# light_module_v1.net
KiCad netlist of a schematic drawn in EAGLE
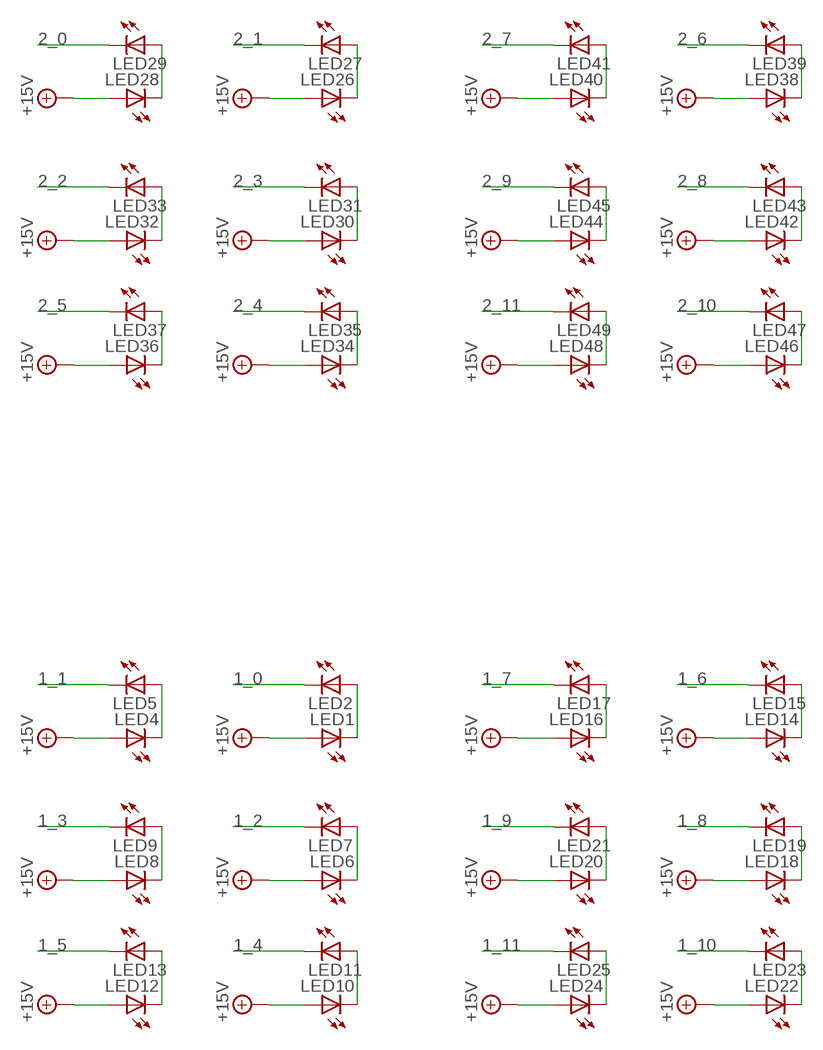
[diagram p0: schematic, sheet 1]
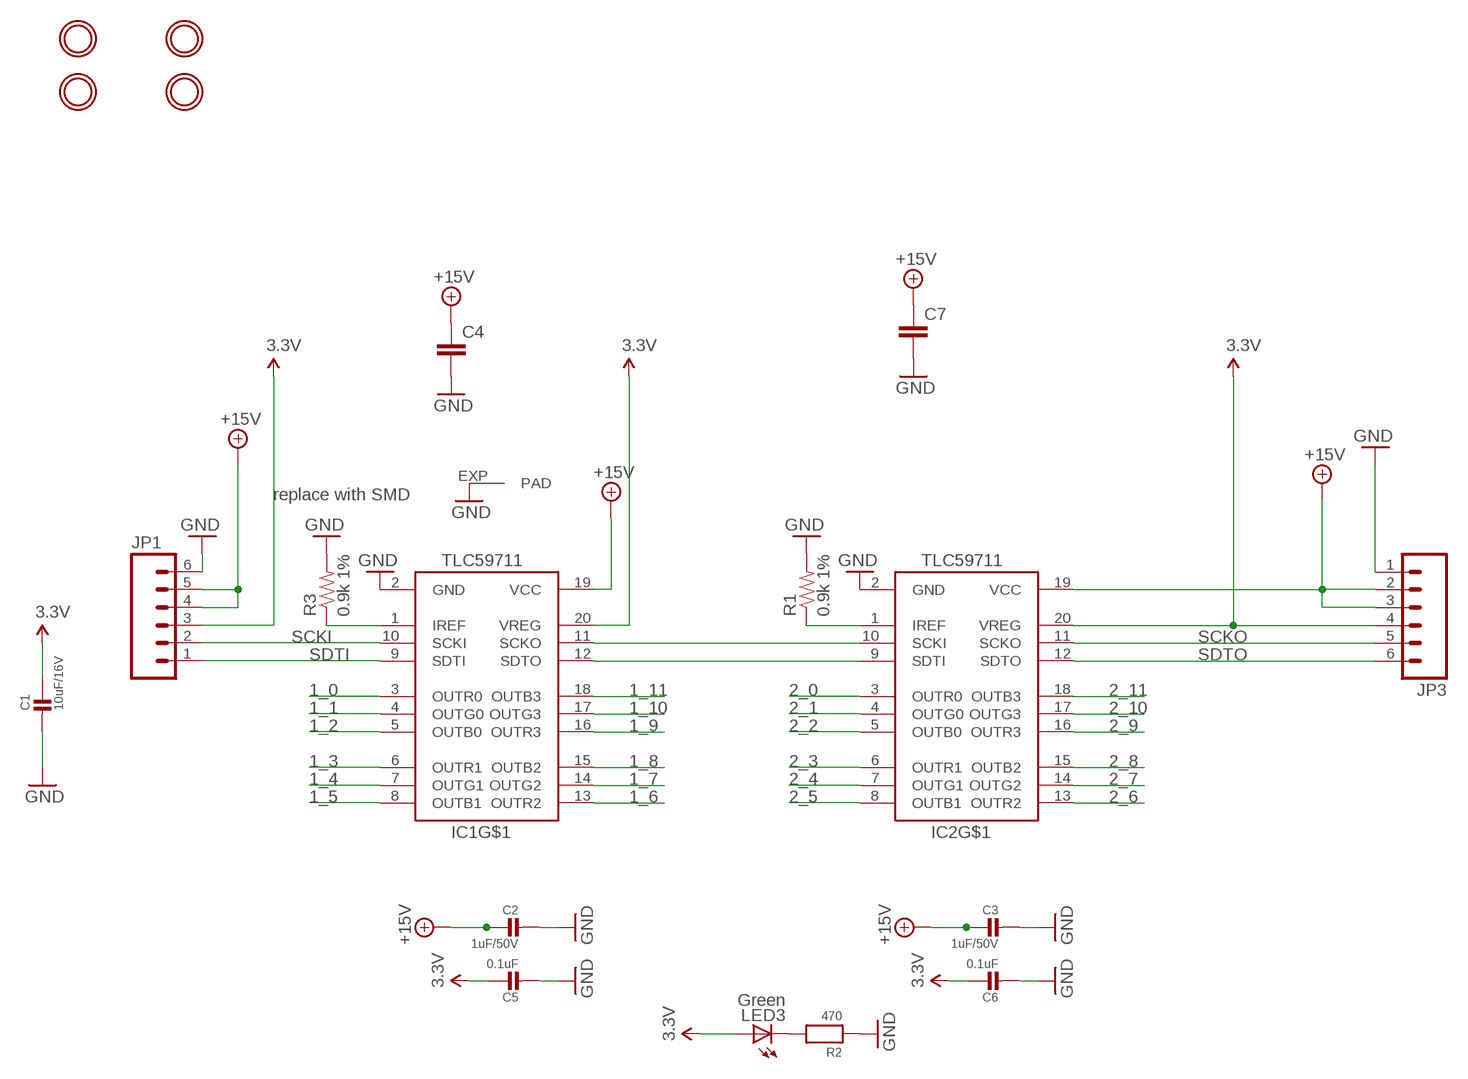
[diagram p1: schematic, sheet 2]

(export (version "E")
  (design (tool "Eeschema 10.0.6"))
  (components
    (comp (ref "C1")
      (value "10uF/16V")
      (footprint "eagle-import:0805")
      (libsource (lib "eagle-import") (part "CAP_CERAMIC0805"))
    )
    (comp (ref "C2")
      (value "1uF/50V")
      (footprint "eagle-import:0805")
      (libsource (lib "eagle-import") (part "CAP_CERAMIC0805"))
    )
    (comp (ref "C3")
      (value "1uF/50V")
      (footprint "eagle-import:0805")
      (libsource (lib "eagle-import") (part "CAP_CERAMIC0805"))
    )
    (comp (ref "C4")
      (value "CAP1206")
      (footprint "eagle-import:1206")
      (libsource (lib "eagle-import") (part "CAP1206"))
    )
    (comp (ref "C5")
      (value "0.1uF")
      (footprint "eagle-import:0805")
      (libsource (lib "eagle-import") (part "CAP_CERAMIC0805"))
    )
    (comp (ref "C6")
      (value "0.1uF")
      (footprint "eagle-import:0805")
      (libsource (lib "eagle-import") (part "CAP_CERAMIC0805"))
    )
    (comp (ref "C7")
      (value "CAP_")
      (footprint "eagle-import:AXIAL-5MM")
      (libsource (lib "eagle-import") (part "CAP_"))
    )
    (comp (ref "IC1")
      (value "TLC59711")
      (footprint "eagle-import:HTSSOP20DAP")
      (libsource (lib "eagle-import") (part "TLC59711"))
    )
    (comp (ref "IC2")
      (value "TLC59711")
      (footprint "eagle-import:HTSSOP20DAP")
      (libsource (lib "eagle-import") (part "TLC59711"))
    )
    (comp (ref "JP1")
      (value "M06SMD-STRAIGHT-COMBO-FEMALE")
      (footprint "eagle-import:1X06_SMD_STRAIGHT_COMBO")
      (libsource (lib "eagle-import") (part "M06SMD-STRAIGHT-COMBO-FEMALE"))
    )
    (comp (ref "JP3")
      (value "M06SMD-STRAIGHT-COMBO-FEMALE")
      (footprint "eagle-import:1X06_SMD_STRAIGHT_COMBO")
      (libsource (lib "eagle-import") (part "M06SMD-STRAIGHT-COMBO-FEMALE"))
    )
    (comp (ref "LED3")
      (value "Green")
      (footprint "eagle-import:CHIP-LED0805")
      (libsource (lib "eagle-import") (part "LEDCHIP-LED0805"))
    )
    (comp (ref "R1")
      (value "0.9k 1%")
      (footprint "eagle-import:1206")
      (libsource (lib "eagle-import") (part "RESISTOR1206"))
    )
    (comp (ref "R2")
      (value "470")
      (footprint "eagle-import:0805")
      (libsource (lib "eagle-import") (part "RESISTOR0805"))
    )
    (comp (ref "R3")
      (value "0.9k 1%")
      (footprint "eagle-import:1206")
      (libsource (lib "eagle-import") (part "RESISTOR1206"))
    )
    (comp (ref "U$1")
      (value "MOUNTINGHOLE2.5")
      (footprint "eagle-import:MOUNTINGHOLE_2.5_PLATED")
      (libsource (lib "eagle-import") (part "MOUNTINGHOLE2.5"))
    )
    (comp (ref "U$2")
      (value "MOUNTINGHOLE2.5")
      (footprint "eagle-import:MOUNTINGHOLE_2.5_PLATED")
      (libsource (lib "eagle-import") (part "MOUNTINGHOLE2.5"))
    )
    (comp (ref "U$3")
      (value "MOUNTINGHOLE2.5")
      (footprint "eagle-import:MOUNTINGHOLE_2.5_PLATED")
      (libsource (lib "eagle-import") (part "MOUNTINGHOLE2.5"))
    )
    (comp (ref "U$4")
      (value "MOUNTINGHOLE2.5")
      (footprint "eagle-import:MOUNTINGHOLE_2.5_PLATED")
      (libsource (lib "eagle-import") (part "MOUNTINGHOLE2.5"))
    )
    (comp (ref "LED1")
      (value "LED")
      (footprint "eagle-import:DS205")
      (libsource (lib "eagle-import") (part "digikey_LED"))
    )
    (comp (ref "LED2")
      (value "LED")
      (footprint "eagle-import:DS205")
      (libsource (lib "eagle-import") (part "digikey_LED"))
    )
    (comp (ref "LED4")
      (value "LED")
      (footprint "eagle-import:DS205")
      (libsource (lib "eagle-import") (part "digikey_LED"))
    )
    (comp (ref "LED5")
      (value "LED")
      (footprint "eagle-import:DS205")
      (libsource (lib "eagle-import") (part "digikey_LED"))
    )
    (comp (ref "LED6")
      (value "LED")
      (footprint "eagle-import:DS205")
      (libsource (lib "eagle-import") (part "digikey_LED"))
    )
    (comp (ref "LED7")
      (value "LED")
      (footprint "eagle-import:DS205")
      (libsource (lib "eagle-import") (part "digikey_LED"))
    )
    (comp (ref "LED8")
      (value "LED")
      (footprint "eagle-import:DS205")
      (libsource (lib "eagle-import") (part "digikey_LED"))
    )
    (comp (ref "LED9")
      (value "LED")
      (footprint "eagle-import:DS205")
      (libsource (lib "eagle-import") (part "digikey_LED"))
    )
    (comp (ref "LED10")
      (value "LED")
      (footprint "eagle-import:DS205")
      (libsource (lib "eagle-import") (part "digikey_LED"))
    )
    (comp (ref "LED11")
      (value "LED")
      (footprint "eagle-import:DS205")
      (libsource (lib "eagle-import") (part "digikey_LED"))
    )
    (comp (ref "LED12")
      (value "LED")
      (footprint "eagle-import:DS205")
      (libsource (lib "eagle-import") (part "digikey_LED"))
    )
    (comp (ref "LED13")
      (value "LED")
      (footprint "eagle-import:DS205")
      (libsource (lib "eagle-import") (part "digikey_LED"))
    )
    (comp (ref "LED14")
      (value "LED")
      (footprint "eagle-import:DS205")
      (libsource (lib "eagle-import") (part "digikey_LED"))
    )
    (comp (ref "LED15")
      (value "LED")
      (footprint "eagle-import:DS205")
      (libsource (lib "eagle-import") (part "digikey_LED"))
    )
    (comp (ref "LED16")
      (value "LED")
      (footprint "eagle-import:DS205")
      (libsource (lib "eagle-import") (part "digikey_LED"))
    )
    (comp (ref "LED17")
      (value "LED")
      (footprint "eagle-import:DS205")
      (libsource (lib "eagle-import") (part "digikey_LED"))
    )
    (comp (ref "LED18")
      (value "LED")
      (footprint "eagle-import:DS205")
      (libsource (lib "eagle-import") (part "digikey_LED"))
    )
    (comp (ref "LED19")
      (value "LED")
      (footprint "eagle-import:DS205")
      (libsource (lib "eagle-import") (part "digikey_LED"))
    )
    (comp (ref "LED20")
      (value "LED")
      (footprint "eagle-import:DS205")
      (libsource (lib "eagle-import") (part "digikey_LED"))
    )
    (comp (ref "LED21")
      (value "LED")
      (footprint "eagle-import:DS205")
      (libsource (lib "eagle-import") (part "digikey_LED"))
    )
    (comp (ref "LED22")
      (value "LED")
      (footprint "eagle-import:DS205")
      (libsource (lib "eagle-import") (part "digikey_LED"))
    )
    (comp (ref "LED23")
      (value "LED")
      (footprint "eagle-import:DS205")
      (libsource (lib "eagle-import") (part "digikey_LED"))
    )
    (comp (ref "LED24")
      (value "LED")
      (footprint "eagle-import:DS205")
      (libsource (lib "eagle-import") (part "digikey_LED"))
    )
    (comp (ref "LED25")
      (value "LED")
      (footprint "eagle-import:DS205")
      (libsource (lib "eagle-import") (part "digikey_LED"))
    )
    (comp (ref "LED26")
      (value "LED")
      (footprint "eagle-import:DS205")
      (libsource (lib "eagle-import") (part "digikey_LED"))
    )
    (comp (ref "LED27")
      (value "LED")
      (footprint "eagle-import:DS205")
      (libsource (lib "eagle-import") (part "digikey_LED"))
    )
    (comp (ref "LED28")
      (value "LED")
      (footprint "eagle-import:DS205")
      (libsource (lib "eagle-import") (part "digikey_LED"))
    )
    (comp (ref "LED29")
      (value "LED")
      (footprint "eagle-import:DS205")
      (libsource (lib "eagle-import") (part "digikey_LED"))
    )
    (comp (ref "LED30")
      (value "LED")
      (footprint "eagle-import:DS205")
      (libsource (lib "eagle-import") (part "digikey_LED"))
    )
    (comp (ref "LED31")
      (value "LED")
      (footprint "eagle-import:DS205")
      (libsource (lib "eagle-import") (part "digikey_LED"))
    )
    (comp (ref "LED32")
      (value "LED")
      (footprint "eagle-import:DS205")
      (libsource (lib "eagle-import") (part "digikey_LED"))
    )
    (comp (ref "LED33")
      (value "LED")
      (footprint "eagle-import:DS205")
      (libsource (lib "eagle-import") (part "digikey_LED"))
    )
    (comp (ref "LED34")
      (value "LED")
      (footprint "eagle-import:DS205")
      (libsource (lib "eagle-import") (part "digikey_LED"))
    )
    (comp (ref "LED35")
      (value "LED")
      (footprint "eagle-import:DS205")
      (libsource (lib "eagle-import") (part "digikey_LED"))
    )
    (comp (ref "LED36")
      (value "LED")
      (footprint "eagle-import:DS205")
      (libsource (lib "eagle-import") (part "digikey_LED"))
    )
    (comp (ref "LED37")
      (value "LED")
      (footprint "eagle-import:DS205")
      (libsource (lib "eagle-import") (part "digikey_LED"))
    )
    (comp (ref "LED38")
      (value "LED")
      (footprint "eagle-import:DS205")
      (libsource (lib "eagle-import") (part "digikey_LED"))
    )
    (comp (ref "LED39")
      (value "LED")
      (footprint "eagle-import:DS205")
      (libsource (lib "eagle-import") (part "digikey_LED"))
    )
    (comp (ref "LED40")
      (value "LED")
      (footprint "eagle-import:DS205")
      (libsource (lib "eagle-import") (part "digikey_LED"))
    )
    (comp (ref "LED41")
      (value "LED")
      (footprint "eagle-import:DS205")
      (libsource (lib "eagle-import") (part "digikey_LED"))
    )
    (comp (ref "LED42")
      (value "LED")
      (footprint "eagle-import:DS205")
      (libsource (lib "eagle-import") (part "digikey_LED"))
    )
    (comp (ref "LED43")
      (value "LED")
      (footprint "eagle-import:DS205")
      (libsource (lib "eagle-import") (part "digikey_LED"))
    )
    (comp (ref "LED44")
      (value "LED")
      (footprint "eagle-import:DS205")
      (libsource (lib "eagle-import") (part "digikey_LED"))
    )
    (comp (ref "LED45")
      (value "LED")
      (footprint "eagle-import:DS205")
      (libsource (lib "eagle-import") (part "digikey_LED"))
    )
    (comp (ref "LED46")
      (value "LED")
      (footprint "eagle-import:DS205")
      (libsource (lib "eagle-import") (part "digikey_LED"))
    )
    (comp (ref "LED47")
      (value "LED")
      (footprint "eagle-import:DS205")
      (libsource (lib "eagle-import") (part "digikey_LED"))
    )
    (comp (ref "LED48")
      (value "LED")
      (footprint "eagle-import:DS205")
      (libsource (lib "eagle-import") (part "digikey_LED"))
    )
    (comp (ref "LED49")
      (value "LED")
      (footprint "eagle-import:DS205")
      (libsource (lib "eagle-import") (part "digikey_LED"))
    )
  )
  (nets
    (net (code "1") (name "+15V") (class "Default")
      (node (ref "C2") (pin "1") (pinfunction "P$1_1") (pintype "passive"))
      (node (ref "C3") (pin "1") (pinfunction "P$1_1") (pintype "passive"))
      (node (ref "C4") (pin "1") (pinfunction "1_1") (pintype "passive"))
      (node (ref "C7") (pin "P$1") (pinfunction "1_P$1") (pintype "passive"))
      (node (ref "IC1") (pin "19") (pinfunction "VCC_19") (pintype "power_in"))
      (node (ref "IC2") (pin "19") (pinfunction "VCC_19") (pintype "power_in"))
      (node (ref "JP1") (pin "4") (pinfunction "4_4") (pintype "passive"))
      (node (ref "JP1") (pin "5") (pinfunction "5_5") (pintype "passive"))
      (node (ref "JP3") (pin "2") (pinfunction "2_2") (pintype "passive"))
      (node (ref "JP3") (pin "3") (pinfunction "3_3") (pintype "passive"))
      (node (ref "LED1") (pin "P$1") (pinfunction "A_P$1") (pintype "passive"))
      (node (ref "LED10") (pin "P$1") (pinfunction "A_P$1") (pintype "passive"))
      (node (ref "LED12") (pin "P$1") (pinfunction "A_P$1") (pintype "passive"))
      (node (ref "LED14") (pin "P$1") (pinfunction "A_P$1") (pintype "passive"))
      (node (ref "LED16") (pin "P$1") (pinfunction "A_P$1") (pintype "passive"))
      (node (ref "LED18") (pin "P$1") (pinfunction "A_P$1") (pintype "passive"))
      (node (ref "LED20") (pin "P$1") (pinfunction "A_P$1") (pintype "passive"))
      (node (ref "LED22") (pin "P$1") (pinfunction "A_P$1") (pintype "passive"))
      (node (ref "LED24") (pin "P$1") (pinfunction "A_P$1") (pintype "passive"))
      (node (ref "LED26") (pin "P$1") (pinfunction "A_P$1") (pintype "passive"))
      (node (ref "LED28") (pin "P$1") (pinfunction "A_P$1") (pintype "passive"))
      (node (ref "LED30") (pin "P$1") (pinfunction "A_P$1") (pintype "passive"))
      (node (ref "LED32") (pin "P$1") (pinfunction "A_P$1") (pintype "passive"))
      (node (ref "LED34") (pin "P$1") (pinfunction "A_P$1") (pintype "passive"))
      (node (ref "LED36") (pin "P$1") (pinfunction "A_P$1") (pintype "passive"))
      (node (ref "LED38") (pin "P$1") (pinfunction "A_P$1") (pintype "passive"))
      (node (ref "LED4") (pin "P$1") (pinfunction "A_P$1") (pintype "passive"))
      (node (ref "LED40") (pin "P$1") (pinfunction "A_P$1") (pintype "passive"))
      (node (ref "LED42") (pin "P$1") (pinfunction "A_P$1") (pintype "passive"))
      (node (ref "LED44") (pin "P$1") (pinfunction "A_P$1") (pintype "passive"))
      (node (ref "LED46") (pin "P$1") (pinfunction "A_P$1") (pintype "passive"))
      (node (ref "LED48") (pin "P$1") (pinfunction "A_P$1") (pintype "passive"))
      (node (ref "LED6") (pin "P$1") (pinfunction "A_P$1") (pintype "passive"))
      (node (ref "LED8") (pin "P$1") (pinfunction "A_P$1") (pintype "passive"))
    )
    (net (code "2") (name "1_0") (class "Default")
      (node (ref "IC1") (pin "3") (pinfunction "OUTR0_3") (pintype "open_collector"))
      (node (ref "LED2") (pin "P$2") (pinfunction "C_P$2") (pintype "passive"))
    )
    (net (code "3") (name "1_1") (class "Default")
      (node (ref "IC1") (pin "4") (pinfunction "OUTG0_4") (pintype "open_collector"))
      (node (ref "LED5") (pin "P$2") (pinfunction "C_P$2") (pintype "passive"))
    )
    (net (code "4") (name "1_2") (class "Default")
      (node (ref "IC1") (pin "5") (pinfunction "OUTB0_5") (pintype "open_collector"))
      (node (ref "LED7") (pin "P$2") (pinfunction "C_P$2") (pintype "passive"))
    )
    (net (code "5") (name "1_3") (class "Default")
      (node (ref "IC1") (pin "6") (pinfunction "OUTR1_6") (pintype "open_collector"))
      (node (ref "LED9") (pin "P$2") (pinfunction "C_P$2") (pintype "passive"))
    )
    (net (code "6") (name "1_4") (class "Default")
      (node (ref "IC1") (pin "7") (pinfunction "OUTG1_7") (pintype "open_collector"))
      (node (ref "LED11") (pin "P$2") (pinfunction "C_P$2") (pintype "passive"))
    )
    (net (code "7") (name "1_5") (class "Default")
      (node (ref "IC1") (pin "8") (pinfunction "OUTB1_8") (pintype "open_collector"))
      (node (ref "LED13") (pin "P$2") (pinfunction "C_P$2") (pintype "passive"))
    )
    (net (code "8") (name "1_6") (class "Default")
      (node (ref "IC1") (pin "13") (pinfunction "OUTR2_13") (pintype "open_collector"))
      (node (ref "LED15") (pin "P$2") (pinfunction "C_P$2") (pintype "passive"))
    )
    (net (code "9") (name "1_7") (class "Default")
      (node (ref "IC1") (pin "14") (pinfunction "OUTG2_14") (pintype "open_collector"))
      (node (ref "LED17") (pin "P$2") (pinfunction "C_P$2") (pintype "passive"))
    )
    (net (code "10") (name "1_8") (class "Default")
      (node (ref "IC1") (pin "15") (pinfunction "OUTB2_15") (pintype "open_collector"))
      (node (ref "LED19") (pin "P$2") (pinfunction "C_P$2") (pintype "passive"))
    )
    (net (code "11") (name "1_9") (class "Default")
      (node (ref "IC1") (pin "16") (pinfunction "OUTR3_16") (pintype "open_collector"))
      (node (ref "LED21") (pin "P$2") (pinfunction "C_P$2") (pintype "passive"))
    )
    (net (code "12") (name "1_10") (class "Default")
      (node (ref "IC1") (pin "17") (pinfunction "OUTG3_17") (pintype "open_collector"))
      (node (ref "LED23") (pin "P$2") (pinfunction "C_P$2") (pintype "passive"))
    )
    (net (code "13") (name "1_11") (class "Default")
      (node (ref "IC1") (pin "18") (pinfunction "OUTB3_18") (pintype "open_collector"))
      (node (ref "LED25") (pin "P$2") (pinfunction "C_P$2") (pintype "passive"))
    )
    (net (code "14") (name "2_0") (class "Default")
      (node (ref "IC2") (pin "3") (pinfunction "OUTR0_3") (pintype "open_collector"))
      (node (ref "LED29") (pin "P$2") (pinfunction "C_P$2") (pintype "passive"))
    )
    (net (code "15") (name "2_1") (class "Default")
      (node (ref "IC2") (pin "4") (pinfunction "OUTG0_4") (pintype "open_collector"))
      (node (ref "LED27") (pin "P$2") (pinfunction "C_P$2") (pintype "passive"))
    )
    (net (code "16") (name "2_2") (class "Default")
      (node (ref "IC2") (pin "5") (pinfunction "OUTB0_5") (pintype "open_collector"))
      (node (ref "LED33") (pin "P$2") (pinfunction "C_P$2") (pintype "passive"))
    )
    (net (code "17") (name "2_3") (class "Default")
      (node (ref "IC2") (pin "6") (pinfunction "OUTR1_6") (pintype "open_collector"))
      (node (ref "LED31") (pin "P$2") (pinfunction "C_P$2") (pintype "passive"))
    )
    (net (code "18") (name "2_4") (class "Default")
      (node (ref "IC2") (pin "7") (pinfunction "OUTG1_7") (pintype "open_collector"))
      (node (ref "LED35") (pin "P$2") (pinfunction "C_P$2") (pintype "passive"))
    )
    (net (code "19") (name "2_5") (class "Default")
      (node (ref "IC2") (pin "8") (pinfunction "OUTB1_8") (pintype "open_collector"))
      (node (ref "LED37") (pin "P$2") (pinfunction "C_P$2") (pintype "passive"))
    )
    (net (code "20") (name "2_6") (class "Default")
      (node (ref "IC2") (pin "13") (pinfunction "OUTR2_13") (pintype "open_collector"))
      (node (ref "LED39") (pin "P$2") (pinfunction "C_P$2") (pintype "passive"))
    )
    (net (code "21") (name "2_7") (class "Default")
      (node (ref "IC2") (pin "14") (pinfunction "OUTG2_14") (pintype "open_collector"))
      (node (ref "LED41") (pin "P$2") (pinfunction "C_P$2") (pintype "passive"))
    )
    (net (code "22") (name "2_8") (class "Default")
      (node (ref "IC2") (pin "15") (pinfunction "OUTB2_15") (pintype "open_collector"))
      (node (ref "LED43") (pin "P$2") (pinfunction "C_P$2") (pintype "passive"))
    )
    (net (code "23") (name "2_9") (class "Default")
      (node (ref "IC2") (pin "16") (pinfunction "OUTR3_16") (pintype "open_collector"))
      (node (ref "LED45") (pin "P$2") (pinfunction "C_P$2") (pintype "passive"))
    )
    (net (code "24") (name "2_10") (class "Default")
      (node (ref "IC2") (pin "17") (pinfunction "OUTG3_17") (pintype "open_collector"))
      (node (ref "LED47") (pin "P$2") (pinfunction "C_P$2") (pintype "passive"))
    )
    (net (code "25") (name "2_11") (class "Default")
      (node (ref "IC2") (pin "18") (pinfunction "OUTB3_18") (pintype "open_collector"))
      (node (ref "LED49") (pin "P$2") (pinfunction "C_P$2") (pintype "passive"))
    )
    (net (code "26") (name "3.3V") (class "Default")
      (node (ref "C1") (pin "1") (pinfunction "P$1_1") (pintype "passive"))
      (node (ref "C5") (pin "1") (pinfunction "P$1_1") (pintype "passive"))
      (node (ref "C6") (pin "1") (pinfunction "P$1_1") (pintype "passive"))
      (node (ref "IC1") (pin "20") (pinfunction "VREG_20") (pintype "bidirectional"))
      (node (ref "IC2") (pin "20") (pinfunction "VREG_20") (pintype "bidirectional"))
      (node (ref "JP1") (pin "3") (pinfunction "3_3") (pintype "passive"))
      (node (ref "JP3") (pin "4") (pinfunction "4_4") (pintype "passive"))
      (node (ref "LED3") (pin "A") (pinfunction "A_A") (pintype "passive"))
    )
    (net (code "27") (name "GND") (class "Default")
      (node (ref "C1") (pin "2") (pinfunction "P$2_2") (pintype "passive"))
      (node (ref "C2") (pin "2") (pinfunction "P$2_2") (pintype "passive"))
      (node (ref "C3") (pin "2") (pinfunction "P$2_2") (pintype "passive"))
      (node (ref "C4") (pin "2") (pinfunction "2_2") (pintype "passive"))
      (node (ref "C5") (pin "2") (pinfunction "P$2_2") (pintype "passive"))
      (node (ref "C6") (pin "2") (pinfunction "P$2_2") (pintype "passive"))
      (node (ref "C7") (pin "P$2") (pinfunction "2_P$2") (pintype "passive"))
      (node (ref "IC1") (pin "2") (pinfunction "GND_2") (pintype "power_in"))
      (node (ref "IC1") (pin "EXP") (pinfunction "PAD_EXP") (pintype "passive"))
      (node (ref "IC2") (pin "2") (pinfunction "GND_2") (pintype "power_in"))
      (node (ref "JP1") (pin "6") (pinfunction "6_6") (pintype "passive"))
      (node (ref "JP3") (pin "1") (pinfunction "1_1") (pintype "passive"))
      (node (ref "R1") (pin "2") (pinfunction "2_2") (pintype "passive"))
      (node (ref "R2") (pin "1") (pinfunction "1_1") (pintype "passive"))
      (node (ref "R3") (pin "2") (pinfunction "2_2") (pintype "passive"))
    )
    (net (code "28") (name "Net-(IC1A-IREF)") (class "Default")
      (node (ref "IC1") (pin "1") (pinfunction "IREF_1") (pintype "bidirectional"))
      (node (ref "R3") (pin "1") (pinfunction "1_1") (pintype "passive"))
    )
    (net (code "29") (name "Net-(IC1A-SCKO)") (class "Default")
      (node (ref "IC1") (pin "11") (pinfunction "SCKO_11") (pintype "output"))
      (node (ref "IC2") (pin "10") (pinfunction "SCKI_10") (pintype "input"))
    )
    (net (code "30") (name "Net-(IC1A-SDTO)") (class "Default")
      (node (ref "IC1") (pin "12") (pinfunction "SDTO_12") (pintype "output"))
      (node (ref "IC2") (pin "9") (pinfunction "SDTI_9") (pintype "input"))
    )
    (net (code "31") (name "Net-(IC2A-IREF)") (class "Default")
      (node (ref "IC2") (pin "1") (pinfunction "IREF_1") (pintype "bidirectional"))
      (node (ref "R1") (pin "1") (pinfunction "1_1") (pintype "passive"))
    )
    (net (code "32") (name "Net-(LED1-C)") (class "Default")
      (node (ref "LED1") (pin "P$2") (pinfunction "C_P$2") (pintype "passive"))
      (node (ref "LED2") (pin "P$1") (pinfunction "A_P$1") (pintype "passive"))
    )
    (net (code "33") (name "Net-(LED3-PadC)") (class "Default")
      (node (ref "LED3") (pin "C") (pinfunction "C_C") (pintype "passive"))
      (node (ref "R2") (pin "2") (pinfunction "2_2") (pintype "passive"))
    )
    (net (code "34") (name "Net-(LED4-C)") (class "Default")
      (node (ref "LED4") (pin "P$2") (pinfunction "C_P$2") (pintype "passive"))
      (node (ref "LED5") (pin "P$1") (pinfunction "A_P$1") (pintype "passive"))
    )
    (net (code "35") (name "Net-(LED6-C)") (class "Default")
      (node (ref "LED6") (pin "P$2") (pinfunction "C_P$2") (pintype "passive"))
      (node (ref "LED7") (pin "P$1") (pinfunction "A_P$1") (pintype "passive"))
    )
    (net (code "36") (name "Net-(LED8-C)") (class "Default")
      (node (ref "LED8") (pin "P$2") (pinfunction "C_P$2") (pintype "passive"))
      (node (ref "LED9") (pin "P$1") (pinfunction "A_P$1") (pintype "passive"))
    )
    (net (code "37") (name "Net-(LED10-C)") (class "Default")
      (node (ref "LED10") (pin "P$2") (pinfunction "C_P$2") (pintype "passive"))
      (node (ref "LED11") (pin "P$1") (pinfunction "A_P$1") (pintype "passive"))
    )
    (net (code "38") (name "Net-(LED12-C)") (class "Default")
      (node (ref "LED12") (pin "P$2") (pinfunction "C_P$2") (pintype "passive"))
      (node (ref "LED13") (pin "P$1") (pinfunction "A_P$1") (pintype "passive"))
    )
    (net (code "39") (name "Net-(LED14-C)") (class "Default")
      (node (ref "LED14") (pin "P$2") (pinfunction "C_P$2") (pintype "passive"))
      (node (ref "LED15") (pin "P$1") (pinfunction "A_P$1") (pintype "passive"))
    )
    (net (code "40") (name "Net-(LED16-C)") (class "Default")
      (node (ref "LED16") (pin "P$2") (pinfunction "C_P$2") (pintype "passive"))
      (node (ref "LED17") (pin "P$1") (pinfunction "A_P$1") (pintype "passive"))
    )
    (net (code "41") (name "Net-(LED18-C)") (class "Default")
      (node (ref "LED18") (pin "P$2") (pinfunction "C_P$2") (pintype "passive"))
      (node (ref "LED19") (pin "P$1") (pinfunction "A_P$1") (pintype "passive"))
    )
    (net (code "42") (name "Net-(LED20-C)") (class "Default")
      (node (ref "LED20") (pin "P$2") (pinfunction "C_P$2") (pintype "passive"))
      (node (ref "LED21") (pin "P$1") (pinfunction "A_P$1") (pintype "passive"))
    )
    (net (code "43") (name "Net-(LED22-C)") (class "Default")
      (node (ref "LED22") (pin "P$2") (pinfunction "C_P$2") (pintype "passive"))
      (node (ref "LED23") (pin "P$1") (pinfunction "A_P$1") (pintype "passive"))
    )
    (net (code "44") (name "Net-(LED24-C)") (class "Default")
      (node (ref "LED24") (pin "P$2") (pinfunction "C_P$2") (pintype "passive"))
      (node (ref "LED25") (pin "P$1") (pinfunction "A_P$1") (pintype "passive"))
    )
    (net (code "45") (name "Net-(LED26-C)") (class "Default")
      (node (ref "LED26") (pin "P$2") (pinfunction "C_P$2") (pintype "passive"))
      (node (ref "LED27") (pin "P$1") (pinfunction "A_P$1") (pintype "passive"))
    )
    (net (code "46") (name "Net-(LED28-C)") (class "Default")
      (node (ref "LED28") (pin "P$2") (pinfunction "C_P$2") (pintype "passive"))
      (node (ref "LED29") (pin "P$1") (pinfunction "A_P$1") (pintype "passive"))
    )
    (net (code "47") (name "Net-(LED30-C)") (class "Default")
      (node (ref "LED30") (pin "P$2") (pinfunction "C_P$2") (pintype "passive"))
      (node (ref "LED31") (pin "P$1") (pinfunction "A_P$1") (pintype "passive"))
    )
    (net (code "48") (name "Net-(LED32-C)") (class "Default")
      (node (ref "LED32") (pin "P$2") (pinfunction "C_P$2") (pintype "passive"))
      (node (ref "LED33") (pin "P$1") (pinfunction "A_P$1") (pintype "passive"))
    )
    (net (code "49") (name "Net-(LED34-C)") (class "Default")
      (node (ref "LED34") (pin "P$2") (pinfunction "C_P$2") (pintype "passive"))
      (node (ref "LED35") (pin "P$1") (pinfunction "A_P$1") (pintype "passive"))
    )
    (net (code "50") (name "Net-(LED36-C)") (class "Default")
      (node (ref "LED36") (pin "P$2") (pinfunction "C_P$2") (pintype "passive"))
      (node (ref "LED37") (pin "P$1") (pinfunction "A_P$1") (pintype "passive"))
    )
    (net (code "51") (name "Net-(LED38-C)") (class "Default")
      (node (ref "LED38") (pin "P$2") (pinfunction "C_P$2") (pintype "passive"))
      (node (ref "LED39") (pin "P$1") (pinfunction "A_P$1") (pintype "passive"))
    )
    (net (code "52") (name "Net-(LED40-C)") (class "Default")
      (node (ref "LED40") (pin "P$2") (pinfunction "C_P$2") (pintype "passive"))
      (node (ref "LED41") (pin "P$1") (pinfunction "A_P$1") (pintype "passive"))
    )
    (net (code "53") (name "Net-(LED42-C)") (class "Default")
      (node (ref "LED42") (pin "P$2") (pinfunction "C_P$2") (pintype "passive"))
      (node (ref "LED43") (pin "P$1") (pinfunction "A_P$1") (pintype "passive"))
    )
    (net (code "54") (name "Net-(LED44-C)") (class "Default")
      (node (ref "LED44") (pin "P$2") (pinfunction "C_P$2") (pintype "passive"))
      (node (ref "LED45") (pin "P$1") (pinfunction "A_P$1") (pintype "passive"))
    )
    (net (code "55") (name "Net-(LED46-C)") (class "Default")
      (node (ref "LED46") (pin "P$2") (pinfunction "C_P$2") (pintype "passive"))
      (node (ref "LED47") (pin "P$1") (pinfunction "A_P$1") (pintype "passive"))
    )
    (net (code "56") (name "Net-(LED48-C)") (class "Default")
      (node (ref "LED48") (pin "P$2") (pinfunction "C_P$2") (pintype "passive"))
      (node (ref "LED49") (pin "P$1") (pinfunction "A_P$1") (pintype "passive"))
    )
    (net (code "57") (name "SCKI") (class "Default")
      (node (ref "IC1") (pin "10") (pinfunction "SCKI_10") (pintype "input"))
      (node (ref "JP1") (pin "2") (pinfunction "2_2") (pintype "passive"))
    )
    (net (code "58") (name "SCKO") (class "Default")
      (node (ref "IC2") (pin "11") (pinfunction "SCKO_11") (pintype "output"))
      (node (ref "JP3") (pin "5") (pinfunction "5_5") (pintype "passive"))
    )
    (net (code "59") (name "SDTI") (class "Default")
      (node (ref "IC1") (pin "9") (pinfunction "SDTI_9") (pintype "input"))
      (node (ref "JP1") (pin "1") (pinfunction "1_1") (pintype "passive"))
    )
    (net (code "60") (name "SDTO") (class "Default")
      (node (ref "IC2") (pin "12") (pinfunction "SDTO_12") (pintype "output"))
      (node (ref "JP3") (pin "6") (pinfunction "6_6") (pintype "passive"))
    )
  )
)
